# ax5043_feather.net
KiCad netlist of a schematic drawn in EAGLE
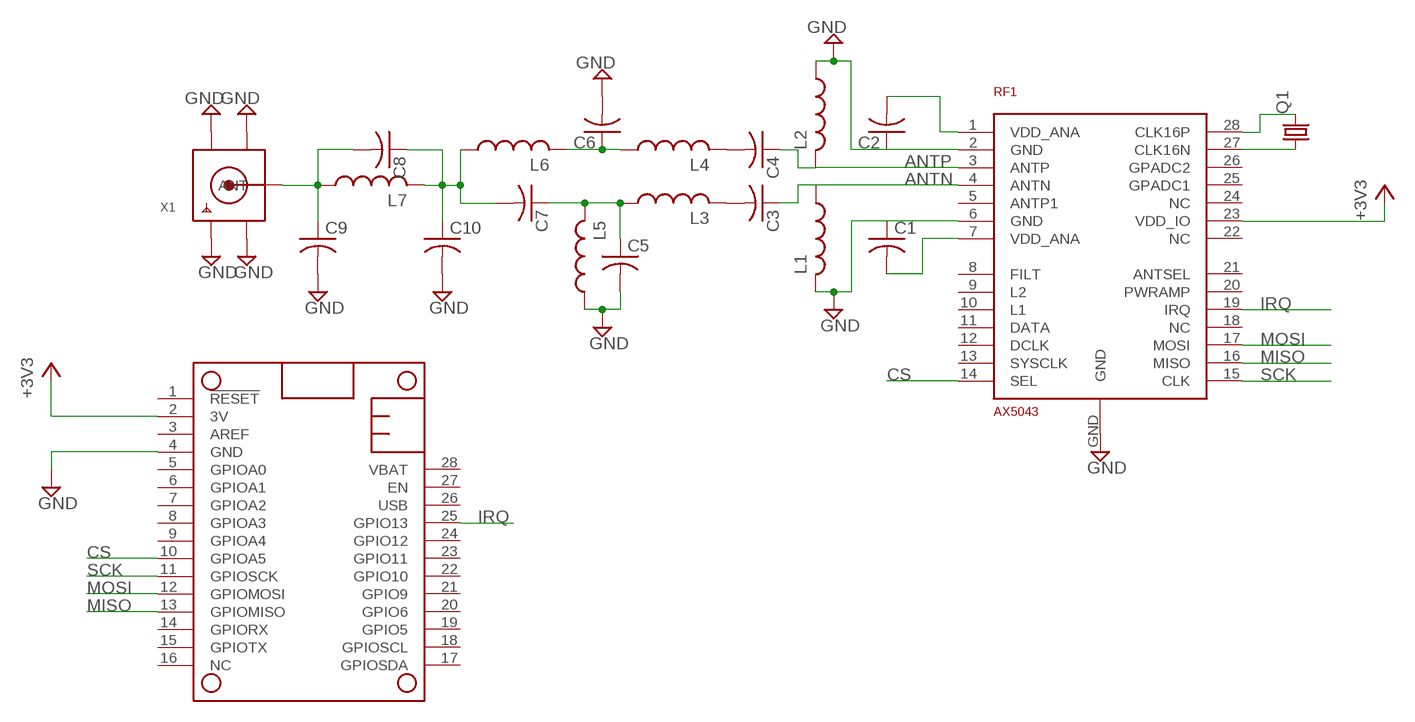
[diagram p0: schematic, sheet 1]

(export (version "E")
  (design (tool "Eeschema 10.0.6"))
  (components
    (comp (ref "C1")
      (value "C-USC0603K")
      (footprint "eagle-import:C0603K")
      (libsource (lib "eagle-import") (part "C-USC0603K"))
    )
    (comp (ref "C2")
      (value "C-USC0603K")
      (footprint "eagle-import:C0603K")
      (libsource (lib "eagle-import") (part "C-USC0603K"))
    )
    (comp (ref "C3")
      (value "C-USC0603K")
      (footprint "eagle-import:C0603K")
      (libsource (lib "eagle-import") (part "C-USC0603K"))
    )
    (comp (ref "C4")
      (value "C-USC0603K")
      (footprint "eagle-import:C0603K")
      (libsource (lib "eagle-import") (part "C-USC0603K"))
    )
    (comp (ref "C5")
      (value "C-USC0603K")
      (footprint "eagle-import:C0603K")
      (libsource (lib "eagle-import") (part "C-USC0603K"))
    )
    (comp (ref "C6")
      (value "C-USC0603K")
      (footprint "eagle-import:C0603K")
      (libsource (lib "eagle-import") (part "C-USC0603K"))
    )
    (comp (ref "C7")
      (value "C-USC0603K")
      (footprint "eagle-import:C0603K")
      (libsource (lib "eagle-import") (part "C-USC0603K"))
    )
    (comp (ref "C8")
      (value "C-USC0603K")
      (footprint "eagle-import:C0603K")
      (libsource (lib "eagle-import") (part "C-USC0603K"))
    )
    (comp (ref "C9")
      (value "C-USC0603K")
      (footprint "eagle-import:C0603K")
      (libsource (lib "eagle-import") (part "C-USC0603K"))
    )
    (comp (ref "C10")
      (value "C-USC0603K")
      (footprint "eagle-import:C0603K")
      (libsource (lib "eagle-import") (part "C-USC0603K"))
    )
    (comp (ref "L1")
      (value "L-US0603K")
      (footprint "eagle-import:C0603K")
      (libsource (lib "eagle-import") (part "L-US0603K"))
    )
    (comp (ref "L2")
      (value "L-US0603K")
      (footprint "eagle-import:C0603K")
      (libsource (lib "eagle-import") (part "L-US0603K"))
    )
    (comp (ref "L3")
      (value "L-US0603K")
      (footprint "eagle-import:C0603K")
      (libsource (lib "eagle-import") (part "L-US0603K"))
    )
    (comp (ref "L4")
      (value "L-US0603K")
      (footprint "eagle-import:C0603K")
      (libsource (lib "eagle-import") (part "L-US0603K"))
    )
    (comp (ref "L5")
      (value "L-US0603K")
      (footprint "eagle-import:C0603K")
      (libsource (lib "eagle-import") (part "L-US0603K"))
    )
    (comp (ref "L6")
      (value "L-US0603K")
      (footprint "eagle-import:C0603K")
      (libsource (lib "eagle-import") (part "L-US0603K"))
    )
    (comp (ref "L7")
      (value "L-US0603K")
      (footprint "eagle-import:C0603K")
      (libsource (lib "eagle-import") (part "L-US0603K"))
    )
    (comp (ref "MS1")
      (value "FEATHERWING")
      (footprint "eagle-import:FEATHERWING")
      (libsource (lib "eagle-import") (part "FEATHERWING"))
    )
    (comp (ref "Q1")
      (value "CRYSTALCTS406")
      (footprint "eagle-import:CTS406")
      (libsource (lib "eagle-import") (part "CRYSTALCTS406"))
    )
    (comp (ref "RF1")
      (value "AX5043")
      (footprint "eagle-import:QFN28-5X5")
      (libsource (lib "eagle-import") (part "AX5043"))
    )
    (comp (ref "X1")
      (value "SMACONNECTOR_EDGE_UFL")
      (footprint "eagle-import:SMA_EDGELAUNCH_UFL")
      (libsource (lib "eagle-import") (part "SMACONNECTOR_EDGE_UFL"))
    )
  )
  (nets
    (net (code "1") (name "+3V3") (class "Default")
      (node (ref "MS1") (pin "2") (pinfunction "3V_2") (pintype "power_in"))
      (node (ref "RF1") (pin "23") (pinfunction "VDD_IO_23") (pintype "bidirectional"))
    )
    (net (code "2") (name "/ANTN") (class "Default")
      (node (ref "C3") (pin "1") (pinfunction "1_1") (pintype "passive"))
      (node (ref "L1") (pin "1") (pinfunction "1_1") (pintype "passive"))
      (node (ref "RF1") (pin "4") (pinfunction "ANTN_4") (pintype "bidirectional"))
    )
    (net (code "3") (name "/ANTP") (class "Default")
      (node (ref "C4") (pin "1") (pinfunction "1_1") (pintype "passive"))
      (node (ref "L2") (pin "2") (pinfunction "2_2") (pintype "passive"))
      (node (ref "RF1") (pin "3") (pinfunction "ANTP_3") (pintype "bidirectional"))
    )
    (net (code "4") (name "/CS") (class "Default")
      (node (ref "MS1") (pin "10") (pinfunction "GPIOA5_10") (pintype "bidirectional"))
      (node (ref "RF1") (pin "14") (pinfunction "SEL_14") (pintype "bidirectional"))
    )
    (net (code "5") (name "/IRQ") (class "Default")
      (node (ref "MS1") (pin "25") (pinfunction "GPIO13_25") (pintype "bidirectional"))
      (node (ref "RF1") (pin "19") (pinfunction "IRQ_19") (pintype "bidirectional"))
    )
    (net (code "6") (name "/MISO") (class "Default")
      (node (ref "MS1") (pin "13") (pinfunction "GPIOMISO_13") (pintype "bidirectional"))
      (node (ref "RF1") (pin "16") (pinfunction "MISO_16") (pintype "bidirectional"))
    )
    (net (code "7") (name "/MOSI") (class "Default")
      (node (ref "MS1") (pin "12") (pinfunction "GPIOMOSI_12") (pintype "bidirectional"))
      (node (ref "RF1") (pin "17") (pinfunction "MOSI_17") (pintype "bidirectional"))
    )
    (net (code "8") (name "/SCK") (class "Default")
      (node (ref "MS1") (pin "11") (pinfunction "GPIOSCK_11") (pintype "bidirectional"))
      (node (ref "RF1") (pin "15") (pinfunction "CLK_15") (pintype "bidirectional"))
    )
    (net (code "9") (name "/USB") (class "Default")
      (node (ref "MS1") (pin "26") (pinfunction "USB_26") (pintype "power_in"))
    )
    (net (code "10") (name "/VBAT") (class "Default")
      (node (ref "MS1") (pin "28") (pinfunction "VBAT_28") (pintype "power_in"))
    )
    (net (code "11") (name "GND") (class "Default")
      (node (ref "C1") (pin "1") (pinfunction "1_1") (pintype "passive"))
      (node (ref "C10") (pin "2") (pinfunction "2_2") (pintype "passive"))
      (node (ref "C2") (pin "1") (pinfunction "1_1") (pintype "passive"))
      (node (ref "C5") (pin "2") (pinfunction "2_2") (pintype "passive"))
      (node (ref "C6") (pin "2") (pinfunction "2_2") (pintype "passive"))
      (node (ref "C9") (pin "2") (pinfunction "2_2") (pintype "passive"))
      (node (ref "L1") (pin "2") (pinfunction "2_2") (pintype "passive"))
      (node (ref "L2") (pin "1") (pinfunction "1_1") (pintype "passive"))
      (node (ref "L5") (pin "1") (pinfunction "1_1") (pintype "passive"))
      (node (ref "MS1") (pin "4") (pinfunction "GND_4") (pintype "power_in"))
      (node (ref "RF1") (pin "2") (pinfunction "GND_2") (pintype "bidirectional"))
      (node (ref "RF1") (pin "6") (pinfunction "GND_6") (pintype "bidirectional"))
      (node (ref "RF1") (pin "GND") (pinfunction "GND_GND") (pintype "bidirectional"))
      (node (ref "X1") (pin "GND@1") (pinfunction "GND1_GND@1") (pintype "power_in"))
      (node (ref "X1") (pin "GND@2") (pinfunction "GND2_GND@2") (pintype "power_in"))
      (node (ref "X1") (pin "GND@3") (pinfunction "GND3_GND@3") (pintype "power_in"))
      (node (ref "X1") (pin "GND@4") (pinfunction "GND4_GND@4") (pintype "power_in"))
    )
    (net (code "12") (name "Net-(C1-Pad2)") (class "Default")
      (node (ref "C1") (pin "2") (pinfunction "2_2") (pintype "passive"))
      (node (ref "RF1") (pin "7") (pinfunction "VDD_ANA_7") (pintype "bidirectional"))
    )
    (net (code "13") (name "Net-(C2-Pad2)") (class "Default")
      (node (ref "C2") (pin "2") (pinfunction "2_2") (pintype "passive"))
      (node (ref "RF1") (pin "1") (pinfunction "VDD_ANA_1") (pintype "bidirectional"))
    )
    (net (code "14") (name "Net-(C3-Pad2)") (class "Default")
      (node (ref "C3") (pin "2") (pinfunction "2_2") (pintype "passive"))
      (node (ref "L3") (pin "2") (pinfunction "2_2") (pintype "passive"))
    )
    (net (code "15") (name "Net-(C4-Pad2)") (class "Default")
      (node (ref "C4") (pin "2") (pinfunction "2_2") (pintype "passive"))
      (node (ref "L4") (pin "2") (pinfunction "2_2") (pintype "passive"))
    )
    (net (code "16") (name "Net-(C5-Pad1)") (class "Default")
      (node (ref "C5") (pin "1") (pinfunction "1_1") (pintype "passive"))
      (node (ref "C7") (pin "1") (pinfunction "1_1") (pintype "passive"))
      (node (ref "L3") (pin "1") (pinfunction "1_1") (pintype "passive"))
      (node (ref "L5") (pin "2") (pinfunction "2_2") (pintype "passive"))
    )
    (net (code "17") (name "Net-(C6-Pad1)") (class "Default")
      (node (ref "C6") (pin "1") (pinfunction "1_1") (pintype "passive"))
      (node (ref "L4") (pin "1") (pinfunction "1_1") (pintype "passive"))
      (node (ref "L6") (pin "2") (pinfunction "2_2") (pintype "passive"))
    )
    (net (code "18") (name "Net-(C10-Pad1)") (class "Default")
      (node (ref "C10") (pin "1") (pinfunction "1_1") (pintype "passive"))
      (node (ref "C7") (pin "2") (pinfunction "2_2") (pintype "passive"))
      (node (ref "C8") (pin "1") (pinfunction "1_1") (pintype "passive"))
      (node (ref "L6") (pin "1") (pinfunction "1_1") (pintype "passive"))
      (node (ref "L7") (pin "2") (pinfunction "2_2") (pintype "passive"))
    )
    (net (code "19") (name "Net-(Q1-2)") (class "Default")
      (node (ref "Q1") (pin "3") (pinfunction "2_3") (pintype "passive"))
      (node (ref "RF1") (pin "28") (pinfunction "CLK16P_28") (pintype "bidirectional"))
    )
    (net (code "20") (name "Net-(RF1-CLK16N)") (class "Default")
      (node (ref "Q1") (pin "1") (pinfunction "1_1") (pintype "passive"))
      (node (ref "RF1") (pin "27") (pinfunction "CLK16N_27") (pintype "bidirectional"))
    )
    (net (code "21") (name "Net-(X1-ANT)") (class "Default")
      (node (ref "C8") (pin "2") (pinfunction "2_2") (pintype "passive"))
      (node (ref "C9") (pin "1") (pinfunction "1_1") (pintype "passive"))
      (node (ref "L7") (pin "1") (pinfunction "1_1") (pintype "passive"))
      (node (ref "X1") (pin "P") (pinfunction "ANT_P") (pintype "bidirectional"))
    )
    (net (code "22") (name "unconnected-(MS1-AREF-Pad3)") (class "Default")
      (node (ref "MS1") (pin "3") (pinfunction "AREF_3") (pintype "passive"))
    )
    (net (code "23") (name "unconnected-(MS1-EN-Pad27)") (class "Default")
      (node (ref "MS1") (pin "27") (pinfunction "EN_27") (pintype "passive"))
    )
    (net (code "24") (name "unconnected-(MS1-GPIO5-Pad19)") (class "Default")
      (node (ref "MS1") (pin "19") (pinfunction "GPIO5_19") (pintype "bidirectional"))
    )
    (net (code "25") (name "unconnected-(MS1-GPIO6-Pad20)") (class "Default")
      (node (ref "MS1") (pin "20") (pinfunction "GPIO6_20") (pintype "bidirectional"))
    )
    (net (code "26") (name "unconnected-(MS1-GPIO9-Pad21)") (class "Default")
      (node (ref "MS1") (pin "21") (pinfunction "GPIO9_21") (pintype "bidirectional"))
    )
    (net (code "27") (name "unconnected-(MS1-GPIO10-Pad22)") (class "Default")
      (node (ref "MS1") (pin "22") (pinfunction "GPIO10_22") (pintype "bidirectional"))
    )
    (net (code "28") (name "unconnected-(MS1-GPIO11-Pad23)") (class "Default")
      (node (ref "MS1") (pin "23") (pinfunction "GPIO11_23") (pintype "bidirectional"))
    )
    (net (code "29") (name "unconnected-(MS1-GPIO12-Pad24)") (class "Default")
      (node (ref "MS1") (pin "24") (pinfunction "GPIO12_24") (pintype "bidirectional"))
    )
    (net (code "30") (name "unconnected-(MS1-GPIOA0-Pad5)") (class "Default")
      (node (ref "MS1") (pin "5") (pinfunction "GPIOA0_5") (pintype "bidirectional"))
    )
    (net (code "31") (name "unconnected-(MS1-GPIOA1-Pad6)") (class "Default")
      (node (ref "MS1") (pin "6") (pinfunction "GPIOA1_6") (pintype "bidirectional"))
    )
    (net (code "32") (name "unconnected-(MS1-GPIOA2-Pad7)") (class "Default")
      (node (ref "MS1") (pin "7") (pinfunction "GPIOA2_7") (pintype "bidirectional"))
    )
    (net (code "33") (name "unconnected-(MS1-GPIOA3-Pad8)") (class "Default")
      (node (ref "MS1") (pin "8") (pinfunction "GPIOA3_8") (pintype "bidirectional"))
    )
    (net (code "34") (name "unconnected-(MS1-GPIOA4-Pad9)") (class "Default")
      (node (ref "MS1") (pin "9") (pinfunction "GPIOA4_9") (pintype "bidirectional"))
    )
    (net (code "35") (name "unconnected-(MS1-GPIORX-Pad14)") (class "Default")
      (node (ref "MS1") (pin "14") (pinfunction "GPIORX_14") (pintype "bidirectional"))
    )
    (net (code "36") (name "unconnected-(MS1-GPIOSCL-Pad18)") (class "Default")
      (node (ref "MS1") (pin "18") (pinfunction "GPIOSCL_18") (pintype "bidirectional"))
    )
    (net (code "37") (name "unconnected-(MS1-GPIOSDA-Pad17)") (class "Default")
      (node (ref "MS1") (pin "17") (pinfunction "GPIOSDA_17") (pintype "bidirectional"))
    )
    (net (code "38") (name "unconnected-(MS1-GPIOTX-Pad15)") (class "Default")
      (node (ref "MS1") (pin "15") (pinfunction "GPIOTX_15") (pintype "bidirectional"))
    )
    (net (code "39") (name "unconnected-(MS1-NC-Pad16)") (class "Default")
      (node (ref "MS1") (pin "16") (pinfunction "NC_16") (pintype "passive"))
    )
    (net (code "40") (name "unconnected-(MS1-~{RESET}-Pad1)") (class "Default")
      (node (ref "MS1") (pin "1") (pinfunction "~{RESET}_1") (pintype "input"))
    )
    (net (code "41") (name "unconnected-(RF1-ANTP1-Pad5)") (class "Default")
      (node (ref "RF1") (pin "5") (pinfunction "ANTP1_5") (pintype "bidirectional"))
    )
    (net (code "42") (name "unconnected-(RF1-ANTSEL-Pad21)") (class "Default")
      (node (ref "RF1") (pin "21") (pinfunction "ANTSEL_21") (pintype "bidirectional"))
    )
    (net (code "43") (name "unconnected-(RF1-DATA-Pad11)") (class "Default")
      (node (ref "RF1") (pin "11") (pinfunction "DATA_11") (pintype "bidirectional"))
    )
    (net (code "44") (name "unconnected-(RF1-DCLK-Pad12)") (class "Default")
      (node (ref "RF1") (pin "12") (pinfunction "DCLK_12") (pintype "bidirectional"))
    )
    (net (code "45") (name "unconnected-(RF1-FILT-Pad8)") (class "Default")
      (node (ref "RF1") (pin "8") (pinfunction "FILT_8") (pintype "bidirectional"))
    )
    (net (code "46") (name "unconnected-(RF1-GPADC1-Pad25)") (class "Default")
      (node (ref "RF1") (pin "25") (pinfunction "GPADC1_25") (pintype "bidirectional"))
    )
    (net (code "47") (name "unconnected-(RF1-GPADC2-Pad26)") (class "Default")
      (node (ref "RF1") (pin "26") (pinfunction "GPADC2_26") (pintype "bidirectional"))
    )
    (net (code "48") (name "unconnected-(RF1-L1-Pad10)") (class "Default")
      (node (ref "RF1") (pin "10") (pinfunction "L1_10") (pintype "bidirectional"))
    )
    (net (code "49") (name "unconnected-(RF1-L2-Pad9)") (class "Default")
      (node (ref "RF1") (pin "9") (pinfunction "L2_9") (pintype "bidirectional"))
    )
    (net (code "50") (name "unconnected-(RF1-NC-Pad18)") (class "Default")
      (node (ref "RF1") (pin "18") (pinfunction "NC_18") (pintype "bidirectional"))
    )
    (net (code "51") (name "unconnected-(RF1-NC-Pad22)") (class "Default")
      (node (ref "RF1") (pin "22") (pinfunction "NC_22") (pintype "bidirectional"))
    )
    (net (code "52") (name "unconnected-(RF1-NC-Pad24)") (class "Default")
      (node (ref "RF1") (pin "24") (pinfunction "NC_24") (pintype "bidirectional"))
    )
    (net (code "53") (name "unconnected-(RF1-PWRAMP-Pad20)") (class "Default")
      (node (ref "RF1") (pin "20") (pinfunction "PWRAMP_20") (pintype "bidirectional"))
    )
    (net (code "54") (name "unconnected-(RF1-SYSCLK-Pad13)") (class "Default")
      (node (ref "RF1") (pin "13") (pinfunction "SYSCLK_13") (pintype "bidirectional"))
    )
  )
)
